# LM2596_Adjustable.net
KiCad netlist of a schematic drawn in Altium Designer
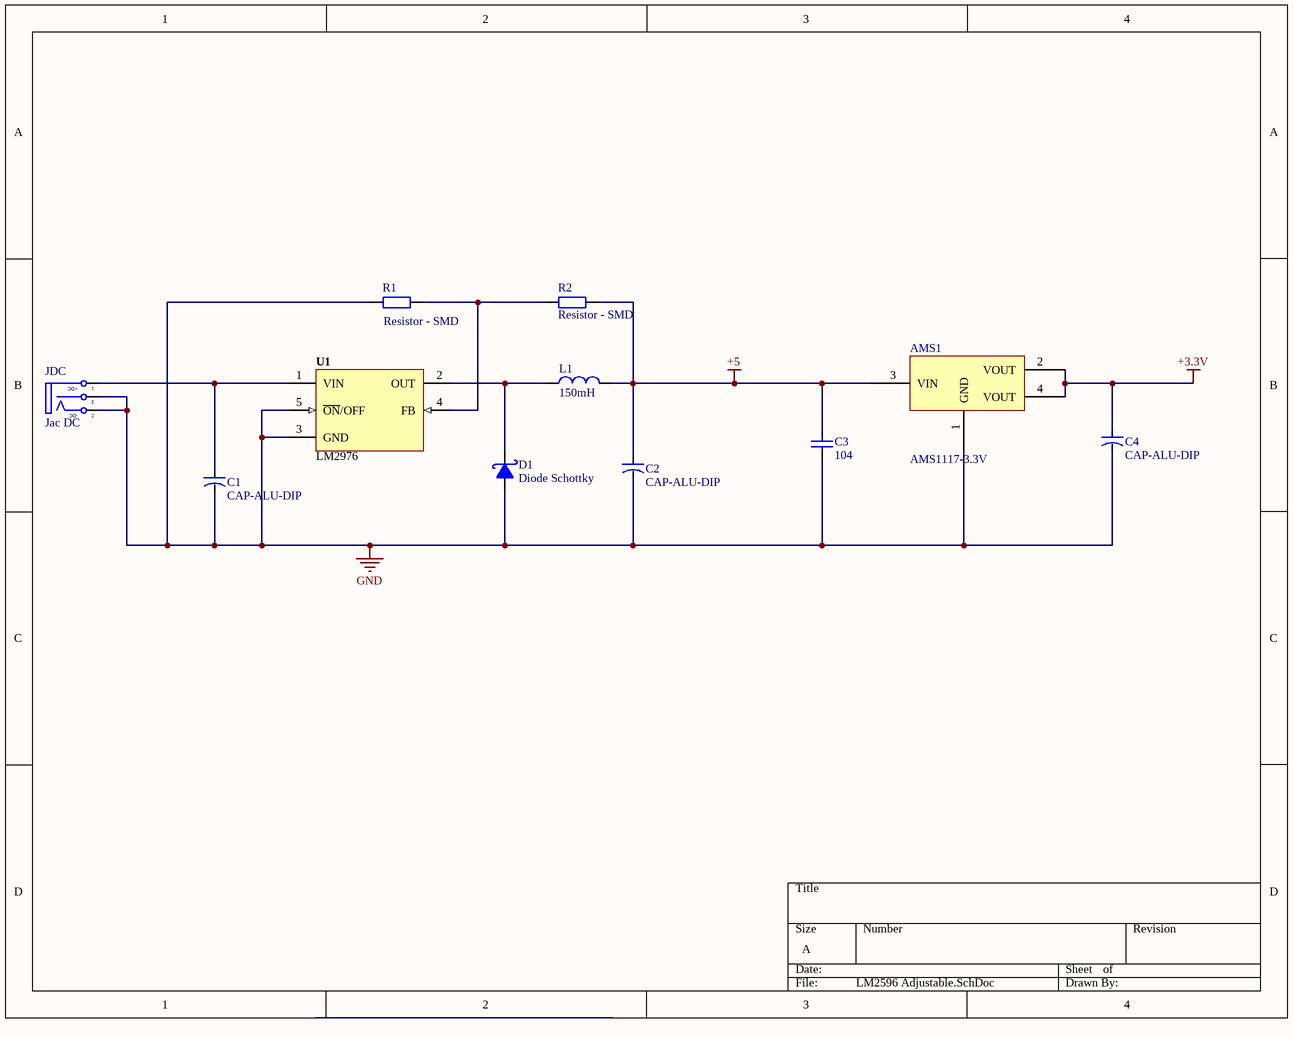
[diagram p0: LM2596 Adjustable.SchDoc]

(export (version "E")
  (design (tool "Eeschema 10.0.6"))
  (components
    (comp (ref "AMS1")
      (value "AMS1117-3.3V")
      (footprint "SOT223")
      (description "Dán")
      (libsource (lib "Altium_Lib_by_KhueNguyenCreator") (part "AMS1117 SMD"))
    )
    (comp (ref "C1")
      (value "CAP-ALU-DIP")
      (footprint "CA-ALU-2.54")
      (description "Capacitor (Semiconductor SIM Model)")
      (fields (field (name "PUBLISHER") "Altium Limited"))
      (libsource (lib "My Library") (part "CAP-ALU-DIP"))
    )
    (comp (ref "C2")
      (value "CAP-ALU-DIP")
      (footprint "CA-ALU-2.54")
      (description "Capacitor (Semiconductor SIM Model)")
      (fields (field (name "PUBLISHER") "Altium Limited"))
      (libsource (lib "My Library") (part "CAP-ALU-DIP"))
    )
    (comp (ref "C3")
      (value "104")
      (footprint "CAP_0402")
      (description "Capacitor")
      (fields (field (name "PUBLISHER") "Altium Limited"))
      (libsource (lib "My Library") (part "CapSMD"))
    )
    (comp (ref "C4")
      (value "CAP-ALU-DIP")
      (footprint "CA-ALU-2.54")
      (description "Capacitor (Semiconductor SIM Model)")
      (fields (field (name "PUBLISHER") "Altium Limited"))
      (libsource (lib "My Library") (part "CAP-ALU-DIP"))
    )
    (comp (ref "D1")
      (value "Diode Schottky")
      (footprint "DIO-3A")
      (description "Generic Diode Schottky")
      (libsource (lib "My Library") (part "Diode Schottky"))
    )
    (comp (ref "JDC")
      (value "Jac DC")
      (footprint "DC-IN")
      (description "Jac DC input")
      (libsource (lib "My Library") (part "DCIN"))
    )
    (comp (ref "L1")
      (value "150mH")
      (footprint "L/0.4")
      (description "Inductor")
      (libsource (lib "My Library") (part "L1"))
    )
    (comp (ref "R1")
      (value "Resistor - SMD")
      (footprint "RES-SMD-0101")
      (description "Resistor SMD")
      (fields
        (field (name "MANUFACTURER") "Generic Components")
        (field (name "PUBLISHER") "Altium Hobart Technology Centre")
      )
      (libsource (lib "My Library") (part "Resistor - SMD"))
    )
    (comp (ref "R2")
      (value "Resistor - SMD")
      (footprint "RES-SMD-0101")
      (description "Resistor SMD")
      (fields
        (field (name "MANUFACTURER") "Generic Components")
        (field (name "PUBLISHER") "Altium Hobart Technology Centre")
      )
      (libsource (lib "My Library") (part "Resistor - SMD"))
    )
    (comp (ref "U1") (value "LM2976") (footprint "LM2576t") (libsource (lib "My Library") (part "LM2596")))
  )
  (nets
    (net (code "1") (name "+3.3V") (class "Default")
      (node (ref "AMS1") (pin "2") (pinfunction "VOUT_2") (pintype "passive"))
      (node (ref "AMS1") (pin "4") (pinfunction "VOUT_4") (pintype "passive"))
      (node (ref "C4") (pin "1") (pinfunction "1_1") (pintype "passive"))
    )
    (net (code "2") (name "+5") (class "Default")
      (node (ref "AMS1") (pin "3") (pinfunction "VIN_3") (pintype "passive"))
      (node (ref "C2") (pin "1") (pinfunction "1_1") (pintype "passive"))
      (node (ref "C3") (pin "2") (pinfunction "2_2") (pintype "passive"))
      (node (ref "L1") (pin "2") (pinfunction "2_2") (pintype "passive"))
      (node (ref "R2") (pin "1") (pinfunction "1_1") (pintype "passive"))
    )
    (net (code "3") (name "GND") (class "Default")
      (node (ref "AMS1") (pin "1") (pinfunction "GND_1") (pintype "passive"))
      (node (ref "C1") (pin "2") (pinfunction "2_2") (pintype "passive"))
      (node (ref "C2") (pin "2") (pinfunction "2_2") (pintype "passive"))
      (node (ref "C3") (pin "1") (pinfunction "1_1") (pintype "passive"))
      (node (ref "C4") (pin "2") (pinfunction "2_2") (pintype "passive"))
      (node (ref "D1") (pin "1") (pinfunction "A_1") (pintype "passive"))
      (node (ref "JDC") (pin "2") (pinfunction "TN_2") (pintype "passive"))
      (node (ref "JDC") (pin "3") (pinfunction "S_3") (pintype "power_in"))
      (node (ref "R1") (pin "2") (pinfunction "2_2") (pintype "passive"))
      (node (ref "U1") (pin "3") (pinfunction "GND_3") (pintype "power_in"))
      (node (ref "U1") (pin "5") (pinfunction "~{ON}/OFF_5") (pintype "input"))
    )
    (net (code "4") (name "Net-(D1-K)") (class "Default")
      (node (ref "D1") (pin "2") (pinfunction "K_2") (pintype "passive"))
      (node (ref "L1") (pin "1") (pinfunction "1_1") (pintype "passive"))
      (node (ref "U1") (pin "2") (pinfunction "OUT_2") (pintype "power_in"))
    )
    (net (code "5") (name "Net-(JDC-T)") (class "Default")
      (node (ref "C1") (pin "1") (pinfunction "1_1") (pintype "passive"))
      (node (ref "JDC") (pin "1") (pinfunction "T_1") (pintype "passive"))
      (node (ref "U1") (pin "1") (pinfunction "VIN_1") (pintype "power_in"))
    )
    (net (code "6") (name "Net-(U1-FB)") (class "Default")
      (node (ref "R1") (pin "1") (pinfunction "1_1") (pintype "passive"))
      (node (ref "R2") (pin "2") (pinfunction "2_2") (pintype "passive"))
      (node (ref "U1") (pin "4") (pinfunction "FB_4") (pintype "input"))
    )
  )
)
